# Fauxzer.net
KiCad netlist of a schematic drawn in EAGLE
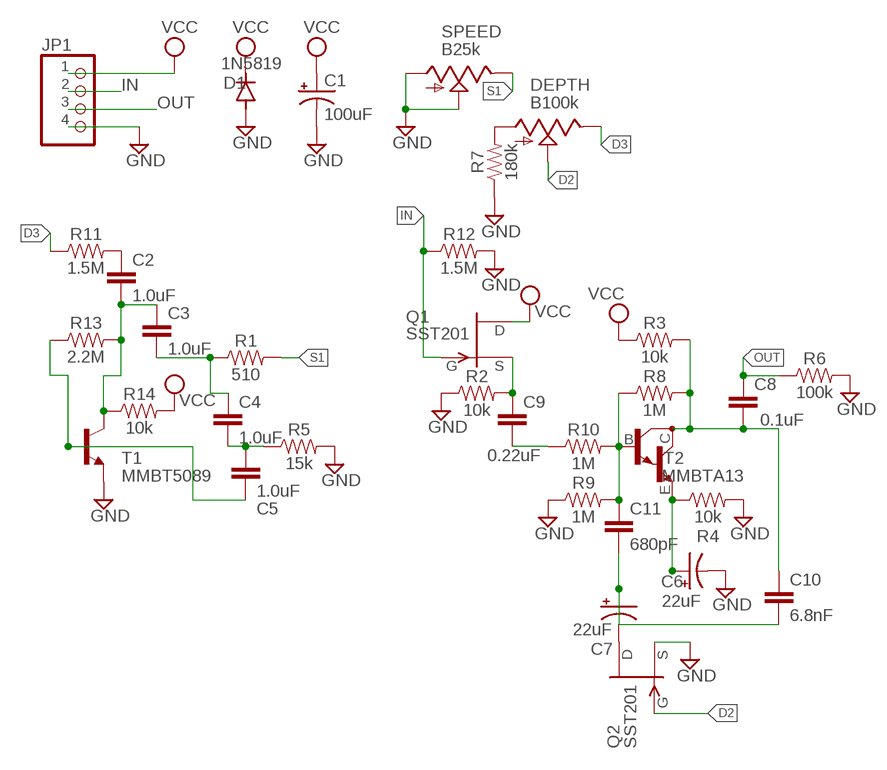
[diagram p0: schematic, sheet 1]

(export (version "E")
  (design (tool "Eeschema 10.0.6"))
  (components
    (comp (ref "C1")
      (value "100uF")
      (footprint "eagle-import:PAN_B_SMD+THRU")
      (libsource (lib "eagle-import") (part "CAP_SMD+THRUPAN_B"))
    )
    (comp (ref "C2")
      (value "1.0uF")
      (footprint "eagle-import:0805")
      (libsource (lib "eagle-import") (part "1.0UF-0805-25V-10%"))
    )
    (comp (ref "C3")
      (value "1.0uF")
      (footprint "eagle-import:0805")
      (libsource (lib "eagle-import") (part "1.0UF-0805-25V-10%"))
    )
    (comp (ref "C4")
      (value "1.0uF")
      (footprint "eagle-import:0805")
      (libsource (lib "eagle-import") (part "1.0UF-0805-25V-10%"))
    )
    (comp (ref "C5")
      (value "1.0uF")
      (footprint "eagle-import:0805")
      (libsource (lib "eagle-import") (part "1.0UF-0805-25V-10%"))
    )
    (comp (ref "C6")
      (value "22uF")
      (footprint "eagle-import:PAN_B_SMD+THRU")
      (libsource (lib "eagle-import") (part "CAP_SMD+THRUPAN_B"))
    )
    (comp (ref "C7")
      (value "22uF")
      (footprint "eagle-import:PAN_B_SMD+THRU")
      (libsource (lib "eagle-import") (part "CAP_SMD+THRUPAN_B"))
    )
    (comp (ref "C8")
      (value "0.1uF")
      (footprint "eagle-import:0603")
      (libsource (lib "eagle-import") (part "0.1UF-0603-25V-(+80/-20%)"))
    )
    (comp (ref "C9")
      (value "0.22uF")
      (footprint "eagle-import:0603")
      (libsource (lib "eagle-import") (part "0.22UF-0603-25V-10%"))
    )
    (comp (ref "C10")
      (value "6.8nF")
      (footprint "eagle-import:0603")
      (libsource (lib "eagle-import") (part "3.3NF-0603-100V-10%"))
    )
    (comp (ref "C11")
      (value "680pF")
      (footprint "eagle-import:0603")
      (libsource (lib "eagle-import") (part "680PF-0603-50V-10%"))
    )
    (comp (ref "D1")
      (value "1N5819")
      (footprint "eagle-import:SOD123")
      (libsource (lib "eagle-import") (part "DIODE-SOD123"))
    )
    (comp (ref "DEPTH")
      (value "B100k")
      (footprint "eagle-import:9MM_SNAP-IN_POT")
      (libsource (lib "eagle-import") (part "9MM_SNAP-IN_POT_"))
    )
    (comp (ref "JP1")
      (value "PINHD-1X4")
      (footprint "eagle-import:1X04")
      (libsource (lib "eagle-import") (part "PINHD-1X4"))
    )
    (comp (ref "Q1")
      (value "SST201")
      (footprint "eagle-import:SOT23")
      (libsource (lib "eagle-import") (part "?20SST1"))
    )
    (comp (ref "Q2")
      (value "SST201")
      (footprint "eagle-import:SOT23")
      (libsource (lib "eagle-import") (part "?20SST1"))
    )
    (comp (ref "R1")
      (value "510")
      (footprint "eagle-import:0603")
      (libsource (lib "eagle-import") (part "470OHM-0603-1/10W-1%"))
    )
    (comp (ref "R2")
      (value "10k")
      (footprint "eagle-import:0603")
      (libsource (lib "eagle-import") (part "10KOHM-0603-1/10W-1%"))
    )
    (comp (ref "R3")
      (value "10k")
      (footprint "eagle-import:0603")
      (libsource (lib "eagle-import") (part "10KOHM-0603-1/10W-1%"))
    )
    (comp (ref "R4")
      (value "10k")
      (footprint "eagle-import:0603")
      (libsource (lib "eagle-import") (part "10KOHM-0603-1/10W-1%"))
    )
    (comp (ref "R5")
      (value "15k")
      (footprint "eagle-import:0603")
      (libsource (lib "eagle-import") (part "15KOHM-0603-1/10W-1%"))
    )
    (comp (ref "R6")
      (value "100k")
      (footprint "eagle-import:0603")
      (libsource (lib "eagle-import") (part "100KOHM-0603-1/10W-1%"))
    )
    (comp (ref "R7")
      (value "180k")
      (footprint "eagle-import:0603")
      (libsource (lib "eagle-import") (part "180KOHM-0603-1/10W-1%"))
    )
    (comp (ref "R8")
      (value "1M")
      (footprint "eagle-import:0603")
      (libsource (lib "eagle-import") (part "1MOHM-0603-1/4W-5%"))
    )
    (comp (ref "R9")
      (value "1M")
      (footprint "eagle-import:0603")
      (libsource (lib "eagle-import") (part "1MOHM-0603-1/4W-5%"))
    )
    (comp (ref "R10")
      (value "1M")
      (footprint "eagle-import:0603")
      (libsource (lib "eagle-import") (part "1MOHM-0603-1/4W-5%"))
    )
    (comp (ref "R11")
      (value "1.5M")
      (footprint "eagle-import:0603")
      (libsource (lib "eagle-import") (part "1.2MOHM-0603-1/10W-1%"))
    )
    (comp (ref "R12")
      (value "1.5M")
      (footprint "eagle-import:0603")
      (libsource (lib "eagle-import") (part "1.2MOHM-0603-1/10W-1%"))
    )
    (comp (ref "R13")
      (value "2.2M")
      (footprint "eagle-import:0603")
      (libsource (lib "eagle-import") (part "2.2KOHM-0603-1/10W-1%"))
    )
    (comp (ref "R14")
      (value "10k")
      (footprint "eagle-import:0603")
      (libsource (lib "eagle-import") (part "10KOHM-0603-1/10W-1%"))
    )
    (comp (ref "SPEED")
      (value "B25k")
      (footprint "eagle-import:9MM_SNAP-IN_POT")
      (libsource (lib "eagle-import") (part "9MM_SNAP-IN_POT_"))
    )
    (comp (ref "T1")
      (value "MMBT5089")
      (footprint "eagle-import:SOT23-BEC")
      (libsource (lib "eagle-import") (part "-NPN-SOT23-BECBC808"))
    )
    (comp (ref "T2")
      (value "MMBTA13")
      (footprint "eagle-import:SOT23-BEC")
      (libsource (lib "eagle-import") (part "-NPN_DARL-SOT23-BECMMBTA13LT1"))
    )
  )
  (nets
    (net (code "1") (name "D2") (class "Default")
      (node (ref "DEPTH") (pin "2") (pinfunction "S_2") (pintype "passive"))
      (node (ref "Q2") (pin "3") (pinfunction "G_3") (pintype "passive"))
    )
    (net (code "2") (name "D3") (class "Default")
      (node (ref "DEPTH") (pin "3") (pinfunction "E_3") (pintype "passive"))
      (node (ref "R11") (pin "1") (pinfunction "1_1") (pintype "passive"))
    )
    (net (code "3") (name "GND") (class "Default")
      (node (ref "C1") (pin "-") (pinfunction "-_-") (pintype "passive"))
      (node (ref "C1") (pin "--") (pinfunction "-_--") (pintype "passive"))
      (node (ref "C6") (pin "-") (pinfunction "-_-") (pintype "passive"))
      (node (ref "C6") (pin "--") (pinfunction "-_--") (pintype "passive"))
      (node (ref "D1") (pin "A") (pinfunction "A_A") (pintype "passive"))
      (node (ref "JP1") (pin "4") (pinfunction "4_4") (pintype "passive"))
      (node (ref "Q2") (pin "2") (pinfunction "S_2") (pintype "passive"))
      (node (ref "R12") (pin "2") (pinfunction "2_2") (pintype "passive"))
      (node (ref "R2") (pin "1") (pinfunction "1_1") (pintype "passive"))
      (node (ref "R4") (pin "2") (pinfunction "2_2") (pintype "passive"))
      (node (ref "R5") (pin "2") (pinfunction "2_2") (pintype "passive"))
      (node (ref "R6") (pin "2") (pinfunction "2_2") (pintype "passive"))
      (node (ref "R7") (pin "1") (pinfunction "1_1") (pintype "passive"))
      (node (ref "R9") (pin "1") (pinfunction "1_1") (pintype "passive"))
      (node (ref "SPEED") (pin "1") (pinfunction "A_1") (pintype "passive"))
      (node (ref "SPEED") (pin "2") (pinfunction "S_2") (pintype "passive"))
      (node (ref "T1") (pin "E") (pinfunction "E_E") (pintype "passive"))
    )
    (net (code "4") (name "IN") (class "Default")
      (node (ref "JP1") (pin "2") (pinfunction "2_2") (pintype "passive"))
      (node (ref "Q1") (pin "3") (pinfunction "G_3") (pintype "passive"))
      (node (ref "R12") (pin "1") (pinfunction "1_1") (pintype "passive"))
    )
    (net (code "5") (name "Net-(C2-Pad1)") (class "Default")
      (node (ref "C2") (pin "1") (pinfunction "1_1") (pintype "passive"))
      (node (ref "R11") (pin "2") (pinfunction "2_2") (pintype "passive"))
    )
    (net (code "6") (name "Net-(C2-Pad2)") (class "Default")
      (node (ref "C2") (pin "2") (pinfunction "2_2") (pintype "passive"))
      (node (ref "C3") (pin "1") (pinfunction "1_1") (pintype "passive"))
      (node (ref "R13") (pin "2") (pinfunction "2_2") (pintype "passive"))
      (node (ref "R14") (pin "1") (pinfunction "1_1") (pintype "passive"))
      (node (ref "T1") (pin "C") (pinfunction "C_C") (pintype "passive"))
    )
    (net (code "7") (name "Net-(C3-Pad2)") (class "Default")
      (node (ref "C3") (pin "2") (pinfunction "2_2") (pintype "passive"))
      (node (ref "C4") (pin "1") (pinfunction "1_1") (pintype "passive"))
      (node (ref "R1") (pin "1") (pinfunction "1_1") (pintype "passive"))
    )
    (net (code "8") (name "Net-(C4-Pad2)") (class "Default")
      (node (ref "C4") (pin "2") (pinfunction "2_2") (pintype "passive"))
      (node (ref "C5") (pin "1") (pinfunction "1_1") (pintype "passive"))
      (node (ref "R5") (pin "1") (pinfunction "1_1") (pintype "passive"))
    )
    (net (code "9") (name "Net-(C5-Pad2)") (class "Default")
      (node (ref "C5") (pin "2") (pinfunction "2_2") (pintype "passive"))
      (node (ref "R13") (pin "1") (pinfunction "1_1") (pintype "passive"))
      (node (ref "T1") (pin "B") (pinfunction "B_B") (pintype "passive"))
    )
    (net (code "10") (name "Net-(C6-+-Pad++)") (class "Default")
      (node (ref "C6") (pin "+") (pinfunction "+_+") (pintype "passive"))
      (node (ref "C6") (pin "++") (pinfunction "+_++") (pintype "passive"))
      (node (ref "R4") (pin "1") (pinfunction "1_1") (pintype "passive"))
      (node (ref "T2") (pin "E") (pinfunction "E_E") (pintype "passive"))
    )
    (net (code "11") (name "Net-(C9-Pad2)") (class "Default")
      (node (ref "C9") (pin "2") (pinfunction "2_2") (pintype "passive"))
      (node (ref "R10") (pin "1") (pinfunction "1_1") (pintype "passive"))
    )
    (net (code "12") (name "Net-(C10-Pad1)") (class "Default")
      (node (ref "C10") (pin "1") (pinfunction "1_1") (pintype "passive"))
      (node (ref "C8") (pin "2") (pinfunction "2_2") (pintype "passive"))
      (node (ref "R3") (pin "2") (pinfunction "2_2") (pintype "passive"))
      (node (ref "R8") (pin "2") (pinfunction "2_2") (pintype "passive"))
      (node (ref "T2") (pin "C") (pinfunction "C_C") (pintype "passive"))
    )
    (net (code "13") (name "Net-(C10-Pad2)") (class "Default")
      (node (ref "C10") (pin "2") (pinfunction "2_2") (pintype "passive"))
      (node (ref "C11") (pin "2") (pinfunction "2_2") (pintype "passive"))
      (node (ref "C7") (pin "+") (pinfunction "+_+") (pintype "passive"))
      (node (ref "C7") (pin "++") (pinfunction "+_++") (pintype "passive"))
    )
    (net (code "14") (name "Net-(C11-Pad1)") (class "Default")
      (node (ref "C11") (pin "1") (pinfunction "1_1") (pintype "passive"))
      (node (ref "R10") (pin "2") (pinfunction "2_2") (pintype "passive"))
      (node (ref "R8") (pin "1") (pinfunction "1_1") (pintype "passive"))
      (node (ref "R9") (pin "2") (pinfunction "2_2") (pintype "passive"))
      (node (ref "T2") (pin "B") (pinfunction "B_B") (pintype "passive"))
    )
    (net (code "15") (name "Net-(DEPTH-A)") (class "Default")
      (node (ref "DEPTH") (pin "1") (pinfunction "A_1") (pintype "passive"))
      (node (ref "R7") (pin "2") (pinfunction "2_2") (pintype "passive"))
    )
    (net (code "16") (name "Net-(Q1-S)") (class "Default")
      (node (ref "C9") (pin "1") (pinfunction "1_1") (pintype "passive"))
      (node (ref "Q1") (pin "2") (pinfunction "S_2") (pintype "passive"))
      (node (ref "R2") (pin "2") (pinfunction "2_2") (pintype "passive"))
    )
    (net (code "17") (name "Net-(Q2-D)") (class "Default")
      (node (ref "C7") (pin "-") (pinfunction "-_-") (pintype "passive"))
      (node (ref "C7") (pin "--") (pinfunction "-_--") (pintype "passive"))
      (node (ref "Q2") (pin "1") (pinfunction "D_1") (pintype "passive"))
    )
    (net (code "18") (name "OUT") (class "Default")
      (node (ref "C8") (pin "1") (pinfunction "1_1") (pintype "passive"))
      (node (ref "JP1") (pin "3") (pinfunction "3_3") (pintype "passive"))
      (node (ref "R6") (pin "1") (pinfunction "1_1") (pintype "passive"))
    )
    (net (code "19") (name "S1") (class "Default")
      (node (ref "R1") (pin "2") (pinfunction "2_2") (pintype "passive"))
      (node (ref "SPEED") (pin "3") (pinfunction "E_3") (pintype "passive"))
    )
    (net (code "20") (name "VCC") (class "Default")
      (node (ref "C1") (pin "+") (pinfunction "+_+") (pintype "passive"))
      (node (ref "C1") (pin "++") (pinfunction "+_++") (pintype "passive"))
      (node (ref "D1") (pin "C") (pinfunction "C_C") (pintype "passive"))
      (node (ref "JP1") (pin "1") (pinfunction "1_1") (pintype "passive"))
      (node (ref "Q1") (pin "1") (pinfunction "D_1") (pintype "passive"))
      (node (ref "R14") (pin "2") (pinfunction "2_2") (pintype "passive"))
      (node (ref "R3") (pin "1") (pinfunction "1_1") (pintype "passive"))
    )
  )
)
